# SNES2USB.net
KiCad netlist of a schematic drawn in EAGLE
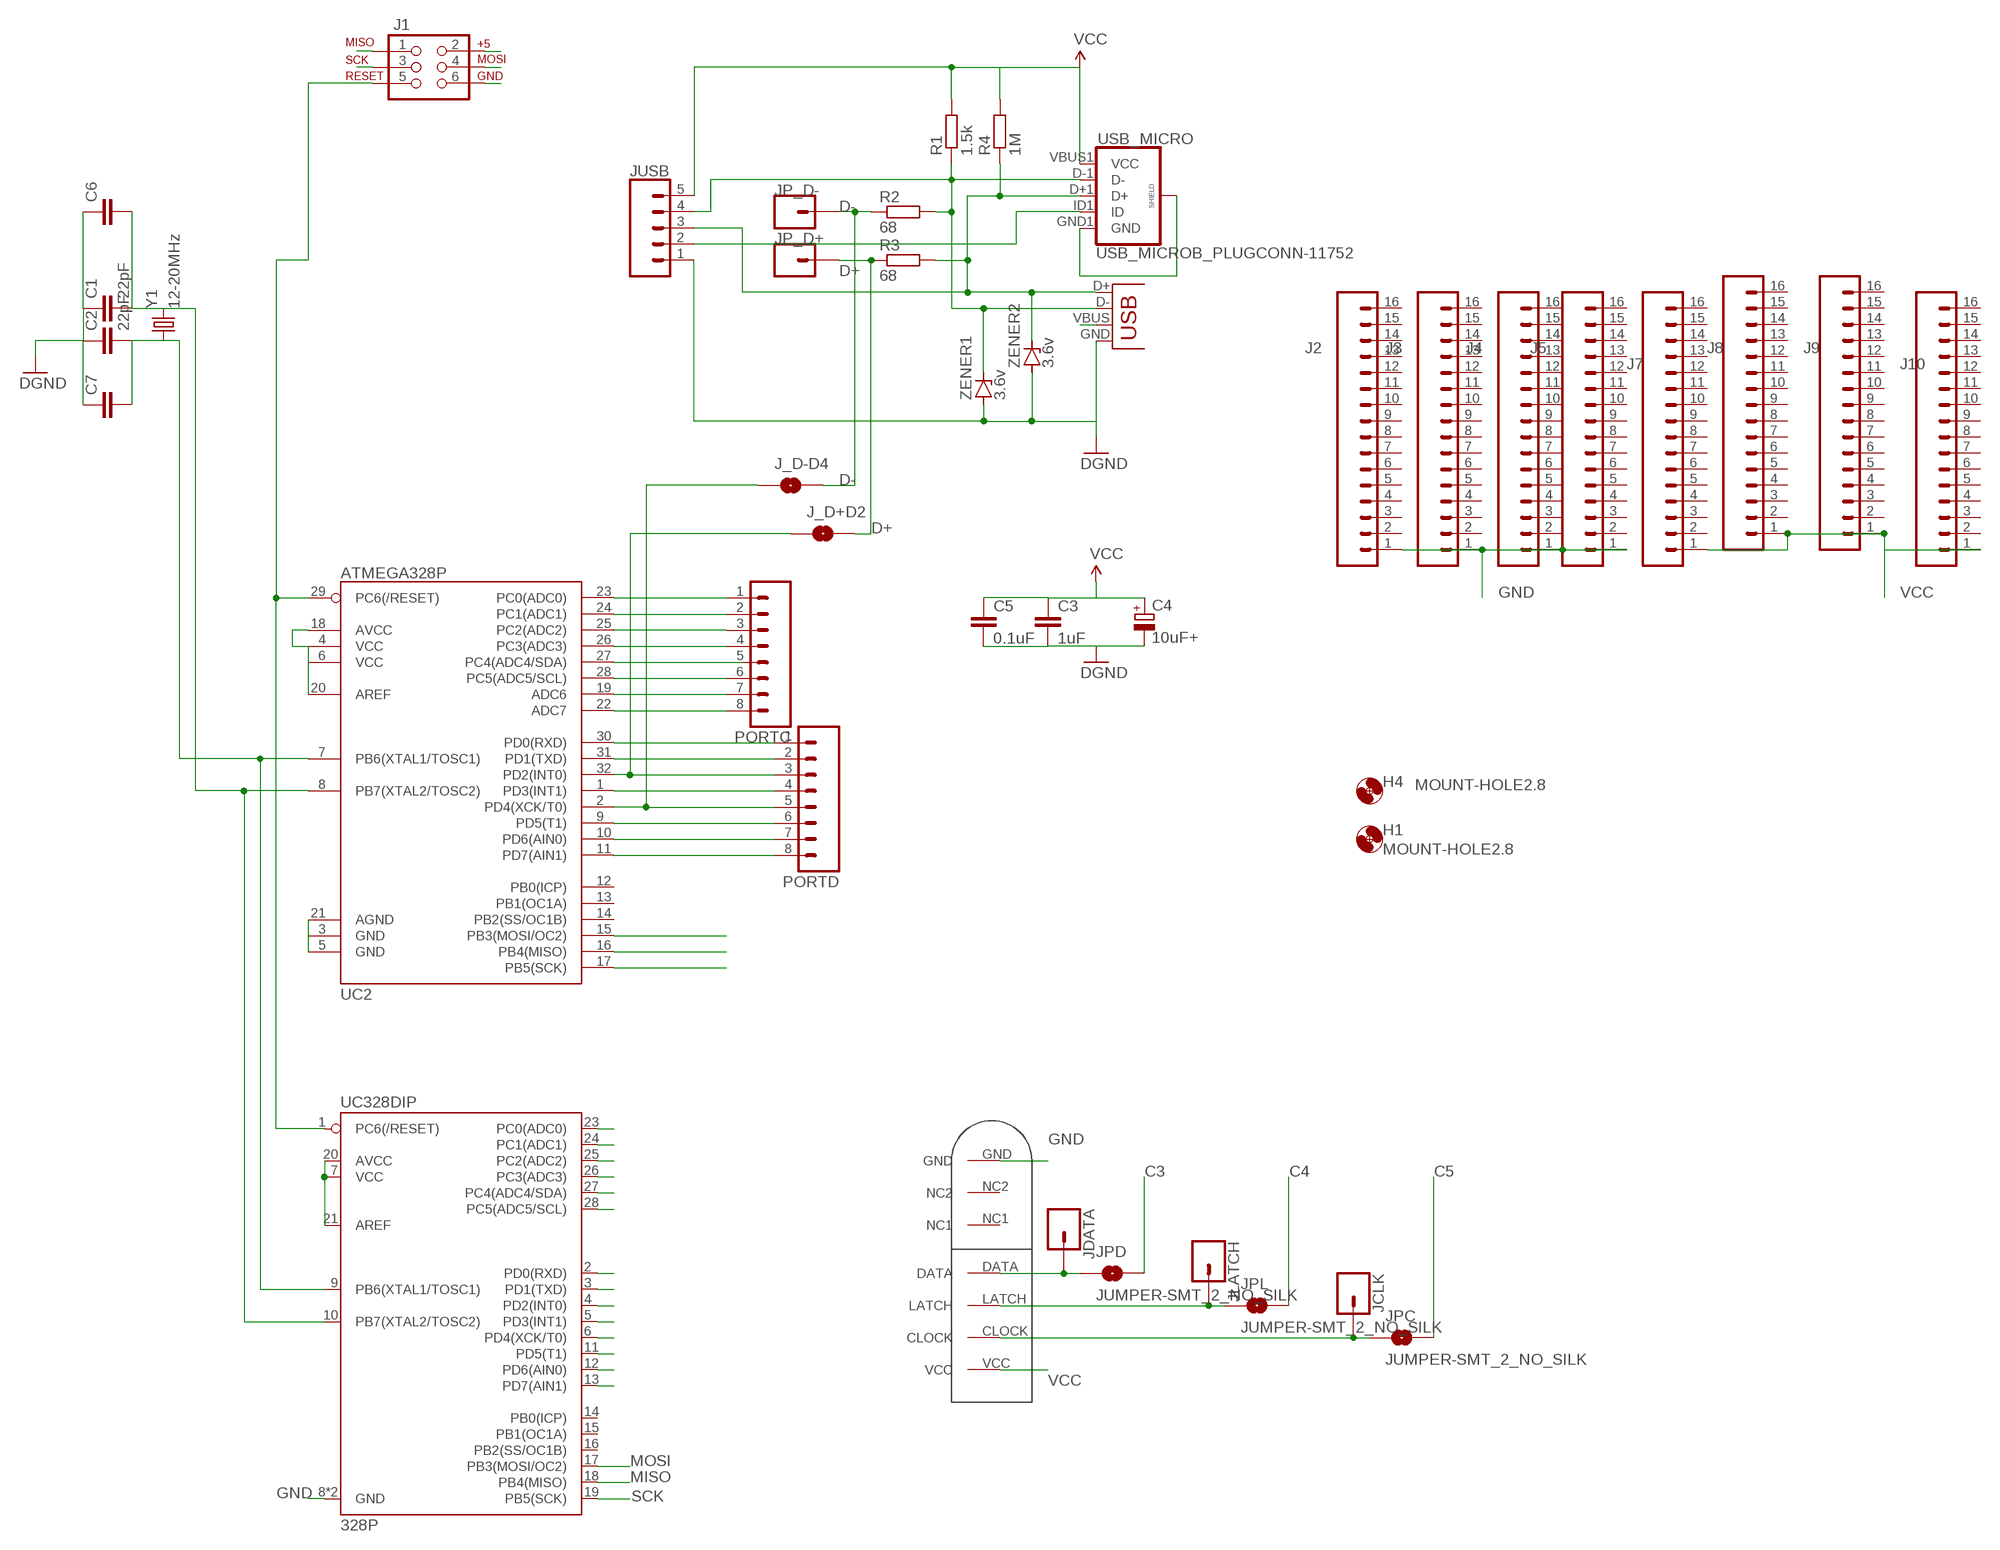
[diagram p0: schematic, sheet 1]

(export (version "E")
  (design (tool "Eeschema 10.0.6"))
  (components
    (comp (ref "C1")
      (value "22pF")
      (footprint "eagle-import:C025-024X044")
      (libsource (lib "eagle-import") (part "C-EU025-024X044"))
    )
    (comp (ref "C2")
      (value "22pF")
      (footprint "eagle-import:C025-024X044")
      (libsource (lib "eagle-import") (part "C-EU025-024X044"))
    )
    (comp (ref "C3")
      (value "1uF")
      (footprint "eagle-import:C025-024X044")
      (libsource (lib "eagle-import") (part "C-EU025-024X044"))
    )
    (comp (ref "C4")
      (value "10uF+")
      (footprint "eagle-import:E2-5")
      (libsource (lib "eagle-import") (part "CPOL-EUE2-5"))
    )
    (comp (ref "C5")
      (value "0.1uF")
      (footprint "eagle-import:C025-024X044")
      (libsource (lib "eagle-import") (part "C-EU025-024X044"))
    )
    (comp (ref "C6")
      (value "C-EUC1206K")
      (footprint "eagle-import:C1206K")
      (libsource (lib "eagle-import") (part "C-EUC1206K"))
    )
    (comp (ref "C7")
      (value "C-EUC1206K")
      (footprint "eagle-import:C1206K")
      (libsource (lib "eagle-import") (part "C-EUC1206K"))
    )
    (comp (ref "H1")
      (value "MOUNT-HOLE2.8")
      (footprint "eagle-import:2,8")
      (libsource (lib "eagle-import") (part "MOUNT-HOLE2.8"))
    )
    (comp (ref "H4")
      (value "MOUNT-HOLE2.8")
      (footprint "eagle-import:2,8")
      (libsource (lib "eagle-import") (part "MOUNT-HOLE2.8"))
    )
    (comp (ref "J1")
      (value "AVR_SPI_PRG_6PTH")
      (footprint "eagle-import:2X3")
      (libsource (lib "eagle-import") (part "AVR_SPI_PRG_6PTH"))
    )
    (comp (ref "J2")
      (value "CONN_161X16_NO_SILK")
      (footprint "eagle-import:1X16_NO_SILK")
      (libsource (lib "eagle-import") (part "CONN_161X16_NO_SILK"))
    )
    (comp (ref "J3")
      (value "CONN_161X16_NO_SILK")
      (footprint "eagle-import:1X16_NO_SILK")
      (libsource (lib "eagle-import") (part "CONN_161X16_NO_SILK"))
    )
    (comp (ref "J4")
      (value "CONN_161X16_NO_SILK")
      (footprint "eagle-import:1X16_NO_SILK")
      (libsource (lib "eagle-import") (part "CONN_161X16_NO_SILK"))
    )
    (comp (ref "J5")
      (value "CONN_161X16_NO_SILK")
      (footprint "eagle-import:1X16_NO_SILK")
      (libsource (lib "eagle-import") (part "CONN_161X16_NO_SILK"))
    )
    (comp (ref "J7")
      (value "CONN_161X16_NO_SILK")
      (footprint "eagle-import:1X16_NO_SILK")
      (libsource (lib "eagle-import") (part "CONN_161X16_NO_SILK"))
    )
    (comp (ref "J8")
      (value "CONN_161X16_NO_SILK")
      (footprint "eagle-import:1X16_NO_SILK")
      (libsource (lib "eagle-import") (part "CONN_161X16_NO_SILK"))
    )
    (comp (ref "J9")
      (value "CONN_161X16_NO_SILK")
      (footprint "eagle-import:1X16_NO_SILK")
      (libsource (lib "eagle-import") (part "CONN_161X16_NO_SILK"))
    )
    (comp (ref "J10")
      (value "CONN_161X16_NO_SILK")
      (footprint "eagle-import:1X16_NO_SILK")
      (libsource (lib "eagle-import") (part "CONN_161X16_NO_SILK"))
    )
    (comp (ref "JCLK")
      (value "CONN_01PTH_NO_SILK_YES_STOP")
      (footprint "eagle-import:1X01_NO_SILK")
      (libsource (lib "eagle-import") (part "CONN_01PTH_NO_SILK_YES_STOP"))
    )
    (comp (ref "JDATA")
      (value "CONN_01PTH_NO_SILK_YES_STOP")
      (footprint "eagle-import:1X01_NO_SILK")
      (libsource (lib "eagle-import") (part "CONN_01PTH_NO_SILK_YES_STOP"))
    )
    (comp (ref "JLATCH")
      (value "CONN_01PTH_NO_SILK_YES_STOP")
      (footprint "eagle-import:1X01_NO_SILK")
      (libsource (lib "eagle-import") (part "CONN_01PTH_NO_SILK_YES_STOP"))
    )
    (comp (ref "JPC")
      (value "JUMPER-SMT_2_NO_SILK")
      (footprint "eagle-import:SMT-JUMPER_2_NO_SILK")
      (libsource (lib "eagle-import") (part "JUMPER-SMT_2_NO_SILK"))
    )
    (comp (ref "JPD")
      (value "JUMPER-SMT_2_NO_SILK")
      (footprint "eagle-import:SMT-JUMPER_2_NO_SILK")
      (libsource (lib "eagle-import") (part "JUMPER-SMT_2_NO_SILK"))
    )
    (comp (ref "JPL")
      (value "JUMPER-SMT_2_NO_SILK")
      (footprint "eagle-import:SMT-JUMPER_2_NO_SILK")
      (libsource (lib "eagle-import") (part "JUMPER-SMT_2_NO_SILK"))
    )
    (comp (ref "JP_D+")
      (value "CONN_01PTH_NO_SILK_YES_STOP")
      (footprint "eagle-import:1X01_NO_SILK")
      (libsource (lib "eagle-import") (part "CONN_01PTH_NO_SILK_YES_STOP"))
    )
    (comp (ref "JP_D-")
      (value "CONN_01PTH_NO_SILK_YES_STOP")
      (footprint "eagle-import:1X01_NO_SILK")
      (libsource (lib "eagle-import") (part "CONN_01PTH_NO_SILK_YES_STOP"))
    )
    (comp (ref "JUSB")
      (value "CONN_05")
      (footprint "eagle-import:1X05")
      (libsource (lib "eagle-import") (part "CONN_05"))
    )
    (comp (ref "J_D+D2")
      (value "JUMPER-PAD-2-NOYES_SILK")
      (footprint "eagle-import:PAD-JUMPER-2-NO_YES_SILK")
      (libsource (lib "eagle-import") (part "JUMPER-PAD-2-NOYES_SILK"))
    )
    (comp (ref "J_D-D4")
      (value "JUMPER-PAD-2-NOYES_SILK")
      (footprint "eagle-import:PAD-JUMPER-2-NO_YES_SILK")
      (libsource (lib "eagle-import") (part "JUMPER-PAD-2-NOYES_SILK"))
    )
    (comp (ref "PORTC")
      (value "M081X08")
      (footprint "eagle-import:1X08")
      (libsource (lib "eagle-import") (part "M081X08"))
    )
    (comp (ref "PORTD")
      (value "M081X08")
      (footprint "eagle-import:1X08")
      (libsource (lib "eagle-import") (part "M081X08"))
    )
    (comp (ref "R1")
      (value "1.5k")
      (footprint "eagle-import:0204V")
      (libsource (lib "eagle-import") (part "R-EU_0204/2V"))
    )
    (comp (ref "R2")
      (value "68")
      (footprint "eagle-import:0204V")
      (libsource (lib "eagle-import") (part "R-EU_0204/2V"))
    )
    (comp (ref "R3")
      (value "68")
      (footprint "eagle-import:0204V")
      (libsource (lib "eagle-import") (part "R-EU_0204/2V"))
    )
    (comp (ref "R4")
      (value "1M")
      (footprint "eagle-import:0204V")
      (libsource (lib "eagle-import") (part "R-EU_0204/2V"))
    )
    (comp (ref "U$1")
      (value "SNES_JOYPAD_CONNECTOR")
      (footprint "eagle-import:SNES_PAD")
      (libsource (lib "eagle-import") (part "SNES_JOYPAD_CONNECTOR"))
    )
    (comp (ref "UC2")
      (value "ATMEGA328P")
      (footprint "eagle-import:TQFP32-08")
      (libsource (lib "eagle-import") (part "ATMEGA328_SMT"))
    )
    (comp (ref "UC328DIP")
      (value "328P")
      (footprint "eagle-import:DIP28")
      (libsource (lib "eagle-import") (part "ATMEGA328P_PDIP"))
    )
    (comp (ref "USB_MICRO")
      (value "USB_MICROB_PLUGCONN-11752")
      (footprint "eagle-import:USB-B-MICRO-SMD_V03")
      (libsource (lib "eagle-import") (part "USB_MICROB_PLUGCONN-11752"))
    )
    (comp (ref "USB_MINI")
      (value "USBSMD")
      (footprint "eagle-import:USB-MINIB")
      (libsource (lib "eagle-import") (part "USBSMD"))
    )
    (comp (ref "Y1")
      (value "12-20MHz")
      (footprint "eagle-import:HC49U-V")
      (libsource (lib "eagle-import") (part "CRYSTALHC49UV"))
    )
    (comp (ref "ZENER1")
      (value "3.6v")
      (footprint "eagle-import:ZDIO-2.5")
      (libsource (lib "eagle-import") (part "ZENER-DIODEZD-2.5"))
    )
    (comp (ref "ZENER2")
      (value "3.6v")
      (footprint "eagle-import:ZDIO-2.5")
      (libsource (lib "eagle-import") (part "ZENER-DIODEZD-2.5"))
    )
  )
  (nets
    (net (code "1") (name "/C0") (class "Default")
      (node (ref "PORTC") (pin "1") (pinfunction "1_1") (pintype "passive"))
      (node (ref "UC2") (pin "23") (pinfunction "PC0(ADC0)_23") (pintype "bidirectional"))
      (node (ref "UC328DIP") (pin "23") (pinfunction "PC0(ADC0)_23") (pintype "bidirectional"))
    )
    (net (code "2") (name "/C1") (class "Default")
      (node (ref "PORTC") (pin "2") (pinfunction "2_2") (pintype "passive"))
      (node (ref "UC2") (pin "24") (pinfunction "PC1(ADC1)_24") (pintype "bidirectional"))
      (node (ref "UC328DIP") (pin "24") (pinfunction "PC1(ADC1)_24") (pintype "bidirectional"))
    )
    (net (code "3") (name "/C3") (class "Default")
      (node (ref "JPD") (pin "2") (pinfunction "2_2") (pintype "passive"))
      (node (ref "PORTC") (pin "4") (pinfunction "4_4") (pintype "passive"))
      (node (ref "UC2") (pin "26") (pinfunction "PC3(ADC3)_26") (pintype "bidirectional"))
      (node (ref "UC328DIP") (pin "26") (pinfunction "PC3(ADC3)_26") (pintype "bidirectional"))
    )
    (net (code "4") (name "/C4") (class "Default")
      (node (ref "JPL") (pin "2") (pinfunction "2_2") (pintype "passive"))
      (node (ref "PORTC") (pin "5") (pinfunction "5_5") (pintype "passive"))
      (node (ref "UC2") (pin "27") (pinfunction "PC4(ADC4/SDA)_27") (pintype "bidirectional"))
      (node (ref "UC328DIP") (pin "27") (pinfunction "PC4(ADC4/SDA)_27") (pintype "bidirectional"))
    )
    (net (code "5") (name "/C5") (class "Default")
      (node (ref "JPC") (pin "2") (pinfunction "2_2") (pintype "passive"))
      (node (ref "PORTC") (pin "6") (pinfunction "6_6") (pintype "passive"))
      (node (ref "UC2") (pin "28") (pinfunction "PC5(ADC5/SCL)_28") (pintype "bidirectional"))
      (node (ref "UC328DIP") (pin "28") (pinfunction "PC5(ADC5/SCL)_28") (pintype "bidirectional"))
    )
    (net (code "6") (name "/D+") (class "Default")
      (node (ref "JP_D+") (pin "1") (pinfunction "1_1") (pintype "passive"))
      (node (ref "J_D+D2") (pin "2") (pinfunction "2_2") (pintype "passive"))
      (node (ref "R3") (pin "1") (pinfunction "1_1") (pintype "passive"))
    )
    (net (code "7") (name "/D-") (class "Default")
      (node (ref "JP_D-") (pin "1") (pinfunction "1_1") (pintype "passive"))
      (node (ref "J_D-D4") (pin "2") (pinfunction "2_2") (pintype "passive"))
      (node (ref "R2") (pin "1") (pinfunction "1_1") (pintype "passive"))
    )
    (net (code "8") (name "/D0") (class "Default")
      (node (ref "PORTD") (pin "1") (pinfunction "1_1") (pintype "passive"))
      (node (ref "UC2") (pin "30") (pinfunction "PD0(RXD)_30") (pintype "bidirectional"))
      (node (ref "UC328DIP") (pin "2") (pinfunction "PD0(RXD)_2") (pintype "bidirectional"))
    )
    (net (code "9") (name "/D1") (class "Default")
      (node (ref "PORTD") (pin "2") (pinfunction "2_2") (pintype "passive"))
      (node (ref "UC2") (pin "31") (pinfunction "PD1(TXD)_31") (pintype "bidirectional"))
      (node (ref "UC328DIP") (pin "3") (pinfunction "PD1(TXD)_3") (pintype "bidirectional"))
    )
    (net (code "10") (name "/D2") (class "Default")
      (node (ref "J_D+D2") (pin "1") (pinfunction "1_1") (pintype "passive"))
      (node (ref "PORTD") (pin "3") (pinfunction "3_3") (pintype "passive"))
      (node (ref "UC2") (pin "32") (pinfunction "PD2(INT0)_32") (pintype "bidirectional"))
      (node (ref "UC328DIP") (pin "4") (pinfunction "PD2(INT0)_4") (pintype "bidirectional"))
    )
    (net (code "11") (name "/D3") (class "Default")
      (node (ref "PORTD") (pin "4") (pinfunction "4_4") (pintype "passive"))
      (node (ref "UC2") (pin "1") (pinfunction "PD3(INT1)_1") (pintype "bidirectional"))
      (node (ref "UC328DIP") (pin "5") (pinfunction "PD3(INT1)_5") (pintype "bidirectional"))
    )
    (net (code "12") (name "/D4") (class "Default")
      (node (ref "J_D-D4") (pin "1") (pinfunction "1_1") (pintype "passive"))
      (node (ref "PORTD") (pin "5") (pinfunction "5_5") (pintype "passive"))
      (node (ref "UC2") (pin "2") (pinfunction "PD4(XCK/T0)_2") (pintype "bidirectional"))
      (node (ref "UC328DIP") (pin "6") (pinfunction "PD4(XCK/T0)_6") (pintype "bidirectional"))
    )
    (net (code "13") (name "/D5") (class "Default")
      (node (ref "PORTD") (pin "6") (pinfunction "6_6") (pintype "passive"))
      (node (ref "UC2") (pin "9") (pinfunction "PD5(T1)_9") (pintype "bidirectional"))
      (node (ref "UC328DIP") (pin "11") (pinfunction "PD5(T1)_11") (pintype "bidirectional"))
    )
    (net (code "14") (name "/D6") (class "Default")
      (node (ref "PORTD") (pin "7") (pinfunction "7_7") (pintype "passive"))
      (node (ref "UC2") (pin "10") (pinfunction "PD6(AIN0)_10") (pintype "bidirectional"))
      (node (ref "UC328DIP") (pin "12") (pinfunction "PD6(AIN0)_12") (pintype "bidirectional"))
    )
    (net (code "15") (name "/D7") (class "Default")
      (node (ref "PORTD") (pin "8") (pinfunction "8_8") (pintype "passive"))
      (node (ref "UC2") (pin "11") (pinfunction "PD7(AIN1)_11") (pintype "bidirectional"))
      (node (ref "UC328DIP") (pin "13") (pinfunction "PD7(AIN1)_13") (pintype "bidirectional"))
    )
    (net (code "16") (name "/MISO") (class "Default")
      (node (ref "J1") (pin "1") (pinfunction "1_1") (pintype "passive"))
      (node (ref "UC2") (pin "16") (pinfunction "PB4(MISO)_16") (pintype "bidirectional"))
      (node (ref "UC328DIP") (pin "18") (pinfunction "PB4(MISO)_18") (pintype "bidirectional"))
    )
    (net (code "17") (name "/MOSI") (class "Default")
      (node (ref "J1") (pin "4") (pinfunction "4_4") (pintype "passive"))
      (node (ref "UC2") (pin "15") (pinfunction "PB3(MOSI/OC2)_15") (pintype "bidirectional"))
      (node (ref "UC328DIP") (pin "17") (pinfunction "PB3(MOSI/OC2)_17") (pintype "bidirectional"))
    )
    (net (code "18") (name "/SCK") (class "Default")
      (node (ref "J1") (pin "3") (pinfunction "3_3") (pintype "passive"))
      (node (ref "UC2") (pin "17") (pinfunction "PB5(SCK)_17") (pintype "bidirectional"))
      (node (ref "UC328DIP") (pin "19") (pinfunction "PB5(SCK)_19") (pintype "bidirectional"))
    )
    (net (code "19") (name "DGND") (class "Default")
      (node (ref "C1") (pin "1") (pinfunction "1_1") (pintype "passive"))
      (node (ref "C2") (pin "1") (pinfunction "1_1") (pintype "passive"))
      (node (ref "C3") (pin "2") (pinfunction "2_2") (pintype "passive"))
      (node (ref "C4") (pin "-") (pinfunction "-_-") (pintype "passive"))
      (node (ref "C5") (pin "2") (pinfunction "2_2") (pintype "passive"))
      (node (ref "C6") (pin "1") (pinfunction "1_1") (pintype "passive"))
      (node (ref "C7") (pin "1") (pinfunction "1_1") (pintype "passive"))
      (node (ref "J1") (pin "6") (pinfunction "6_6") (pintype "passive"))
      (node (ref "J2") (pin "1") (pinfunction "1_1") (pintype "passive"))
      (node (ref "J3") (pin "1") (pinfunction "1_1") (pintype "passive"))
      (node (ref "J4") (pin "1") (pinfunction "1_1") (pintype "passive"))
      (node (ref "J5") (pin "1") (pinfunction "1_1") (pintype "passive"))
      (node (ref "JUSB") (pin "1") (pinfunction "1_1") (pintype "passive"))
      (node (ref "U$1") (pin "GND") (pinfunction "GND_GND") (pintype "bidirectional"))
      (node (ref "UC2") (pin "21") (pinfunction "AGND_21") (pintype "bidirectional"))
      (node (ref "UC2") (pin "3") (pinfunction "GND_3") (pintype "bidirectional"))
      (node (ref "UC2") (pin "5") (pinfunction "GND_5") (pintype "bidirectional"))
      (node (ref "UC328DIP") (pin "22") (pinfunction "GND_22") (pintype "bidirectional"))
      (node (ref "UC328DIP") (pin "8") (pinfunction "GND_8") (pintype "bidirectional"))
      (node (ref "USB_MICRO") (pin "GND1") (pinfunction "GND_GND1") (pintype "bidirectional"))
      (node (ref "USB_MICRO") (pin "SHIELD1") (pinfunction "SHIELD_SHIELD1") (pintype "bidirectional"))
      (node (ref "USB_MICRO") (pin "SHIELD2") (pinfunction "SHIELD_SHIELD2") (pintype "bidirectional"))
      (node (ref "USB_MICRO") (pin "SHIELD3") (pinfunction "SHIELD_SHIELD3") (pintype "bidirectional"))
      (node (ref "USB_MINI") (pin "GND") (pinfunction "GND_GND") (pintype "bidirectional"))
      (node (ref "ZENER1") (pin "A") (pinfunction "A_A") (pintype "passive"))
      (node (ref "ZENER2") (pin "A") (pinfunction "A_A") (pintype "passive"))
    )
    (net (code "20") (name "Net-(JCLK-Pad1)") (class "Default")
      (node (ref "JCLK") (pin "1") (pinfunction "1_1") (pintype "passive"))
      (node (ref "JPC") (pin "1") (pinfunction "1_1") (pintype "passive"))
      (node (ref "U$1") (pin "CLOCK") (pinfunction "CLOCK_CLOCK") (pintype "bidirectional"))
    )
    (net (code "21") (name "Net-(JDATA-Pad1)") (class "Default")
      (node (ref "JDATA") (pin "1") (pinfunction "1_1") (pintype "passive"))
      (node (ref "JPD") (pin "1") (pinfunction "1_1") (pintype "passive"))
      (node (ref "U$1") (pin "DATA") (pinfunction "DATA_DATA") (pintype "bidirectional"))
    )
    (net (code "22") (name "Net-(JLATCH-Pad1)") (class "Default")
      (node (ref "JLATCH") (pin "1") (pinfunction "1_1") (pintype "passive"))
      (node (ref "JPL") (pin "1") (pinfunction "1_1") (pintype "passive"))
      (node (ref "U$1") (pin "LATCH") (pinfunction "LATCH_LATCH") (pintype "bidirectional"))
    )
    (net (code "23") (name "Net-(UC2-ADC6)") (class "Default")
      (node (ref "PORTC") (pin "7") (pinfunction "7_7") (pintype "passive"))
      (node (ref "UC2") (pin "19") (pinfunction "ADC6_19") (pintype "bidirectional"))
    )
    (net (code "24") (name "Net-(UC2-ADC7)") (class "Default")
      (node (ref "PORTC") (pin "8") (pinfunction "8_8") (pintype "passive"))
      (node (ref "UC2") (pin "22") (pinfunction "ADC7_22") (pintype "bidirectional"))
    )
    (net (code "25") (name "Net-(UC2-PB6(XTAL1{slash}TOSC1))") (class "Default")
      (node (ref "C2") (pin "2") (pinfunction "2_2") (pintype "passive"))
      (node (ref "C7") (pin "2") (pinfunction "2_2") (pintype "passive"))
      (node (ref "UC2") (pin "7") (pinfunction "PB6(XTAL1/TOSC1)_7") (pintype "bidirectional"))
      (node (ref "UC328DIP") (pin "9") (pinfunction "PB6(XTAL1/TOSC1)_9") (pintype "bidirectional"))
      (node (ref "Y1") (pin "1") (pinfunction "1_1") (pintype "passive"))
    )
    (net (code "26") (name "Net-(UC2-PB7(XTAL2{slash}TOSC2))") (class "Default")
      (node (ref "C1") (pin "2") (pinfunction "2_2") (pintype "passive"))
      (node (ref "C6") (pin "2") (pinfunction "2_2") (pintype "passive"))
      (node (ref "UC2") (pin "8") (pinfunction "PB7(XTAL2/TOSC2)_8") (pintype "bidirectional"))
      (node (ref "UC328DIP") (pin "10") (pinfunction "PB7(XTAL2/TOSC2)_10") (pintype "bidirectional"))
      (node (ref "Y1") (pin "2") (pinfunction "2_2") (pintype "passive"))
    )
    (net (code "27") (name "Net-(UC2-PC2(ADC2))") (class "Default")
      (node (ref "PORTC") (pin "3") (pinfunction "3_3") (pintype "passive"))
      (node (ref "UC2") (pin "25") (pinfunction "PC2(ADC2)_25") (pintype "bidirectional"))
    )
    (net (code "28") (name "Net-(UC2-PC6({slash}RESET))") (class "Default")
      (node (ref "J1") (pin "5") (pinfunction "5_5") (pintype "passive"))
      (node (ref "UC2") (pin "29") (pinfunction "PC6(/RESET)_29") (pintype "bidirectional"))
      (node (ref "UC328DIP") (pin "1") (pinfunction "PC6(/RESET)_1") (pintype "bidirectional"))
    )
    (net (code "29") (name "Net-(USB_MICRO-D+)") (class "Default")
      (node (ref "JUSB") (pin "3") (pinfunction "3_3") (pintype "passive"))
      (node (ref "R3") (pin "2") (pinfunction "2_2") (pintype "passive"))
      (node (ref "R4") (pin "1") (pinfunction "1_1") (pintype "passive"))
      (node (ref "USB_MICRO") (pin "D+1") (pinfunction "D+_D+1") (pintype "bidirectional"))
      (node (ref "USB_MINI") (pin "D+") (pinfunction "D+_D+") (pintype "bidirectional"))
      (node (ref "ZENER2") (pin "C") (pinfunction "C_C") (pintype "passive"))
    )
    (net (code "30") (name "Net-(USB_MICRO-D-)") (class "Default")
      (node (ref "JUSB") (pin "4") (pinfunction "4_4") (pintype "passive"))
      (node (ref "R1") (pin "1") (pinfunction "1_1") (pintype "passive"))
      (node (ref "R2") (pin "2") (pinfunction "2_2") (pintype "passive"))
      (node (ref "USB_MICRO") (pin "D-1") (pinfunction "D-_D-1") (pintype "bidirectional"))
      (node (ref "USB_MINI") (pin "D-") (pinfunction "D-_D-") (pintype "bidirectional"))
      (node (ref "ZENER1") (pin "C") (pinfunction "C_C") (pintype "passive"))
    )
    (net (code "31") (name "Net-(USB_MICRO-ID)") (class "Default")
      (node (ref "JUSB") (pin "2") (pinfunction "2_2") (pintype "passive"))
      (node (ref "USB_MICRO") (pin "ID1") (pinfunction "ID_ID1") (pintype "bidirectional"))
    )
    (net (code "32") (name "VCC") (class "Default")
      (node (ref "C3") (pin "1") (pinfunction "1_1") (pintype "passive"))
      (node (ref "C4") (pin "+") (pinfunction "+_+") (pintype "passive"))
      (node (ref "C5") (pin "1") (pinfunction "1_1") (pintype "passive"))
      (node (ref "J1") (pin "2") (pinfunction "2_2") (pintype "passive"))
      (node (ref "J10") (pin "1") (pinfunction "1_1") (pintype "passive"))
      (node (ref "J7") (pin "1") (pinfunction "1_1") (pintype "passive"))
      (node (ref "J8") (pin "1") (pinfunction "1_1") (pintype "passive"))
      (node (ref "J9") (pin "1") (pinfunction "1_1") (pintype "passive"))
      (node (ref "JUSB") (pin "5") (pinfunction "5_5") (pintype "passive"))
      (node (ref "R1") (pin "2") (pinfunction "2_2") (pintype "passive"))
      (node (ref "R4") (pin "2") (pinfunction "2_2") (pintype "passive"))
      (node (ref "U$1") (pin "VCC") (pinfunction "VCC_VCC") (pintype "bidirectional"))
      (node (ref "UC2") (pin "18") (pinfunction "AVCC_18") (pintype "bidirectional"))
      (node (ref "UC2") (pin "20") (pinfunction "AREF_20") (pintype "bidirectional"))
      (node (ref "UC2") (pin "4") (pinfunction "VCC_4") (pintype "bidirectional"))
      (node (ref "UC2") (pin "6") (pinfunction "VCC_6") (pintype "bidirectional"))
      (node (ref "UC328DIP") (pin "20") (pinfunction "AVCC_20") (pintype "bidirectional"))
      (node (ref "UC328DIP") (pin "21") (pinfunction "AREF_21") (pintype "bidirectional"))
      (node (ref "UC328DIP") (pin "7") (pinfunction "VCC_7") (pintype "bidirectional"))
      (node (ref "USB_MICRO") (pin "VBUS1") (pinfunction "VCC_VBUS1") (pintype "bidirectional"))
      (node (ref "USB_MINI") (pin "VBUS") (pinfunction "VBUS_VBUS") (pintype "bidirectional"))
    )
    (net (code "33") (name "unconnected-(J2-Pad2)") (class "Default")
      (node (ref "J2") (pin "2") (pinfunction "2_2") (pintype "passive"))
    )
    (net (code "34") (name "unconnected-(J2-Pad3)") (class "Default")
      (node (ref "J2") (pin "3") (pinfunction "3_3") (pintype "passive"))
    )
    (net (code "35") (name "unconnected-(J2-Pad4)") (class "Default")
      (node (ref "J2") (pin "4") (pinfunction "4_4") (pintype "passive"))
    )
    (net (code "36") (name "unconnected-(J2-Pad5)") (class "Default")
      (node (ref "J2") (pin "5") (pinfunction "5_5") (pintype "passive"))
    )
    (net (code "37") (name "unconnected-(J2-Pad6)") (class "Default")
      (node (ref "J2") (pin "6") (pinfunction "6_6") (pintype "passive"))
    )
    (net (code "38") (name "unconnected-(J2-Pad7)") (class "Default")
      (node (ref "J2") (pin "7") (pinfunction "7_7") (pintype "passive"))
    )
    (net (code "39") (name "unconnected-(J2-Pad8)") (class "Default")
      (node (ref "J2") (pin "8") (pinfunction "8_8") (pintype "passive"))
    )
    (net (code "40") (name "unconnected-(J2-Pad9)") (class "Default")
      (node (ref "J2") (pin "9") (pinfunction "9_9") (pintype "passive"))
    )
    (net (code "41") (name "unconnected-(J2-Pad10)") (class "Default")
      (node (ref "J2") (pin "10") (pinfunction "10_10") (pintype "passive"))
    )
    (net (code "42") (name "unconnected-(J2-Pad11)") (class "Default")
      (node (ref "J2") (pin "11") (pinfunction "11_11") (pintype "passive"))
    )
    (net (code "43") (name "unconnected-(J2-Pad12)") (class "Default")
      (node (ref "J2") (pin "12") (pinfunction "12_12") (pintype "passive"))
    )
    (net (code "44") (name "unconnected-(J2-Pad13)") (class "Default")
      (node (ref "J2") (pin "13") (pinfunction "13_13") (pintype "passive"))
    )
    (net (code "45") (name "unconnected-(J2-Pad14)") (class "Default")
      (node (ref "J2") (pin "14") (pinfunction "14_14") (pintype "passive"))
    )
    (net (code "46") (name "unconnected-(J2-Pad15)") (class "Default")
      (node (ref "J2") (pin "15") (pinfunction "15_15") (pintype "passive"))
    )
    (net (code "47") (name "unconnected-(J2-Pad16)") (class "Default")
      (node (ref "J2") (pin "16") (pinfunction "16_16") (pintype "passive"))
    )
    (net (code "48") (name "unconnected-(J3-Pad2)") (class "Default")
      (node (ref "J3") (pin "2") (pinfunction "2_2") (pintype "passive"))
    )
    (net (code "49") (name "unconnected-(J3-Pad3)") (class "Default")
      (node (ref "J3") (pin "3") (pinfunction "3_3") (pintype "passive"))
    )
    (net (code "50") (name "unconnected-(J3-Pad4)") (class "Default")
      (node (ref "J3") (pin "4") (pinfunction "4_4") (pintype "passive"))
    )
    (net (code "51") (name "unconnected-(J3-Pad5)") (class "Default")
      (node (ref "J3") (pin "5") (pinfunction "5_5") (pintype "passive"))
    )
    (net (code "52") (name "unconnected-(J3-Pad6)") (class "Default")
      (node (ref "J3") (pin "6") (pinfunction "6_6") (pintype "passive"))
    )
    (net (code "53") (name "unconnected-(J3-Pad7)") (class "Default")
      (node (ref "J3") (pin "7") (pinfunction "7_7") (pintype "passive"))
    )
    (net (code "54") (name "unconnected-(J3-Pad8)") (class "Default")
      (node (ref "J3") (pin "8") (pinfunction "8_8") (pintype "passive"))
    )
    (net (code "55") (name "unconnected-(J3-Pad9)") (class "Default")
      (node (ref "J3") (pin "9") (pinfunction "9_9") (pintype "passive"))
    )
    (net (code "56") (name "unconnected-(J3-Pad10)") (class "Default")
      (node (ref "J3") (pin "10") (pinfunction "10_10") (pintype "passive"))
    )
    (net (code "57") (name "unconnected-(J3-Pad11)") (class "Default")
      (node (ref "J3") (pin "11") (pinfunction "11_11") (pintype "passive"))
    )
    (net (code "58") (name "unconnected-(J3-Pad12)") (class "Default")
      (node (ref "J3") (pin "12") (pinfunction "12_12") (pintype "passive"))
    )
    (net (code "59") (name "unconnected-(J3-Pad13)") (class "Default")
      (node (ref "J3") (pin "13") (pinfunction "13_13") (pintype "passive"))
    )
    (net (code "60") (name "unconnected-(J3-Pad14)") (class "Default")
      (node (ref "J3") (pin "14") (pinfunction "14_14") (pintype "passive"))
    )
    (net (code "61") (name "unconnected-(J3-Pad15)") (class "Default")
      (node (ref "J3") (pin "15") (pinfunction "15_15") (pintype "passive"))
    )
    (net (code "62") (name "unconnected-(J3-Pad16)") (class "Default")
      (node (ref "J3") (pin "16") (pinfunction "16_16") (pintype "passive"))
    )
    (net (code "63") (name "unconnected-(J4-Pad2)") (class "Default")
      (node (ref "J4") (pin "2") (pinfunction "2_2") (pintype "passive"))
    )
    (net (code "64") (name "unconnected-(J4-Pad3)") (class "Default")
      (node (ref "J4") (pin "3") (pinfunction "3_3") (pintype "passive"))
    )
    (net (code "65") (name "unconnected-(J4-Pad4)") (class "Default")
      (node (ref "J4") (pin "4") (pinfunction "4_4") (pintype "passive"))
    )
    (net (code "66") (name "unconnected-(J4-Pad5)") (class "Default")
      (node (ref "J4") (pin "5") (pinfunction "5_5") (pintype "passive"))
    )
    (net (code "67") (name "unconnected-(J4-Pad6)") (class "Default")
      (node (ref "J4") (pin "6") (pinfunction "6_6") (pintype "passive"))
    )
    (net (code "68") (name "unconnected-(J4-Pad7)") (class "Default")
      (node (ref "J4") (pin "7") (pinfunction "7_7") (pintype "passive"))
    )
    (net (code "69") (name "unconnected-(J4-Pad8)") (class "Default")
      (node (ref "J4") (pin "8") (pinfunction "8_8") (pintype "passive"))
    )
    (net (code "70") (name "unconnected-(J4-Pad9)") (class "Default")
      (node (ref "J4") (pin "9") (pinfunction "9_9") (pintype "passive"))
    )
    (net (code "71") (name "unconnected-(J4-Pad10)") (class "Default")
      (node (ref "J4") (pin "10") (pinfunction "10_10") (pintype "passive"))
    )
    (net (code "72") (name "unconnected-(J4-Pad11)") (class "Default")
      (node (ref "J4") (pin "11") (pinfunction "11_11") (pintype "passive"))
    )
    (net (code "73") (name "unconnected-(J4-Pad12)") (class "Default")
      (node (ref "J4") (pin "12") (pinfunction "12_12") (pintype "passive"))
    )
    (net (code "74") (name "unconnected-(J4-Pad13)") (class "Default")
      (node (ref "J4") (pin "13") (pinfunction "13_13") (pintype "passive"))
    )
    (net (code "75") (name "unconnected-(J4-Pad14)") (class "Default")
      (node (ref "J4") (pin "14") (pinfunction "14_14") (pintype "passive"))
    )
    (net (code "76") (name "unconnected-(J4-Pad15)") (class "Default")
      (node (ref "J4") (pin "15") (pinfunction "15_15") (pintype "passive"))
    )
    (net (code "77") (name "unconnected-(J4-Pad16)") (class "Default")
      (node (ref "J4") (pin "16") (pinfunction "16_16") (pintype "passive"))
    )
    (net (code "78") (name "unconnected-(J5-Pad2)") (class "Default")
      (node (ref "J5") (pin "2") (pinfunction "2_2") (pintype "passive"))
    )
    (net (code "79") (name "unconnected-(J5-Pad3)") (class "Default")
      (node (ref "J5") (pin "3") (pinfunction "3_3") (pintype "passive"))
    )
    (net (code "80") (name "unconnected-(J5-Pad4)") (class "Default")
      (node (ref "J5") (pin "4") (pinfunction "4_4") (pintype "passive"))
    )
    (net (code "81") (name "unconnected-(J5-Pad5)") (class "Default")
      (node (ref "J5") (pin "5") (pinfunction "5_5") (pintype "passive"))
    )
    (net (code "82") (name "unconnected-(J5-Pad6)") (class "Default")
      (node (ref "J5") (pin "6") (pinfunction "6_6") (pintype "passive"))
    )
    (net (code "83") (name "unconnected-(J5-Pad7)") (class "Default")
      (node (ref "J5") (pin "7") (pinfunction "7_7") (pintype "passive"))
    )
    (net (code "84") (name "unconnected-(J5-Pad8)") (class "Default")
      (node (ref "J5") (pin "8") (pinfunction "8_8") (pintype "passive"))
    )
    (net (code "85") (name "unconnected-(J5-Pad9)") (class "Default")
      (node (ref "J5") (pin "9") (pinfunction "9_9") (pintype "passive"))
    )
    (net (code "86") (name "unconnected-(J5-Pad10)") (class "Default")
      (node (ref "J5") (pin "10") (pinfunction "10_10") (pintype "passive"))
    )
    (net (code "87") (name "unconnected-(J5-Pad11)") (class "Default")
      (node (ref "J5") (pin "11") (pinfunction "11_11") (pintype "passive"))
    )
    (net (code "88") (name "unconnected-(J5-Pad12)") (class "Default")
      (node (ref "J5") (pin "12") (pinfunction "12_12") (pintype "passive"))
    )
    (net (code "89") (name "unconnected-(J5-Pad13)") (class "Default")
      (node (ref "J5") (pin "13") (pinfunction "13_13") (pintype "passive"))
    )
    (net (code "90") (name "unconnected-(J5-Pad14)") (class "Default")
      (node (ref "J5") (pin "14") (pinfunction "14_14") (pintype "passive"))
    )
    (net (code "91") (name "unconnected-(J5-Pad15)") (class "Default")
      (node (ref "J5") (pin "15") (pinfunction "15_15") (pintype "passive"))
    )
    (net (code "92") (name "unconnected-(J5-Pad16)") (class "Default")
      (node (ref "J5") (pin "16") (pinfunction "16_16") (pintype "passive"))
    )
    (net (code "93") (name "unconnected-(J7-Pad2)") (class "Default")
      (node (ref "J7") (pin "2") (pinfunction "2_2") (pintype "passive"))
    )
    (net (code "94") (name "unconnected-(J7-Pad3)") (class "Default")
      (node (ref "J7") (pin "3") (pinfunction "3_3") (pintype "passive"))
    )
    (net (code "95") (name "unconnected-(J7-Pad4)") (class "Default")
      (node (ref "J7") (pin "4") (pinfunction "4_4") (pintype "passive"))
    )
    (net (code "96") (name "unconnected-(J7-Pad5)") (class "Default")
      (node (ref "J7") (pin "5") (pinfunction "5_5") (pintype "passive"))
    )
    (net (code "97") (name "unconnected-(J7-Pad6)") (class "Default")
      (node (ref "J7") (pin "6") (pinfunction "6_6") (pintype "passive"))
    )
    (net (code "98") (name "unconnected-(J7-Pad7)") (class "Default")
      (node (ref "J7") (pin "7") (pinfunction "7_7") (pintype "passive"))
    )
    (net (code "99") (name "unconnected-(J7-Pad8)") (class "Default")
      (node (ref "J7") (pin "8") (pinfunction "8_8") (pintype "passive"))
    )
    (net (code "100") (name "unconnected-(J7-Pad9)") (class "Default")
      (node (ref "J7") (pin "9") (pinfunction "9_9") (pintype "passive"))
    )
    (net (code "101") (name "unconnected-(J7-Pad10)") (class "Default")
      (node (ref "J7") (pin "10") (pinfunction "10_10") (pintype "passive"))
    )
    (net (code "102") (name "unconnected-(J7-Pad11)") (class "Default")
      (node (ref "J7") (pin "11") (pinfunction "11_11") (pintype "passive"))
    )
    (net (code "103") (name "unconnected-(J7-Pad12)") (class "Default")
      (node (ref "J7") (pin "12") (pinfunction "12_12") (pintype "passive"))
    )
    (net (code "104") (name "unconnected-(J7-Pad13)") (class "Default")
      (node (ref "J7") (pin "13") (pinfunction "13_13") (pintype "passive"))
    )
    (net (code "105") (name "unconnected-(J7-Pad14)") (class "Default")
      (node (ref "J7") (pin "14") (pinfunction "14_14") (pintype "passive"))
    )
    (net (code "106") (name "unconnected-(J7-Pad15)") (class "Default")
      (node (ref "J7") (pin "15") (pinfunction "15_15") (pintype "passive"))
    )
    (net (code "107") (name "unconnected-(J7-Pad16)") (class "Default")
      (node (ref "J7") (pin "16") (pinfunction "16_16") (pintype "passive"))
    )
    (net (code "108") (name "unconnected-(J8-Pad2)") (class "Default")
      (node (ref "J8") (pin "2") (pinfunction "2_2") (pintype "passive"))
    )
    (net (code "109") (name "unconnected-(J8-Pad3)") (class "Default")
      (node (ref "J8") (pin "3") (pinfunction "3_3") (pintype "passive"))
    )
    (net (code "110") (name "unconnected-(J8-Pad4)") (class "Default")
      (node (ref "J8") (pin "4") (pinfunction "4_4") (pintype "passive"))
    )
    (net (code "111") (name "unconnected-(J8-Pad5)") (class "Default")
      (node (ref "J8") (pin "5") (pinfunction "5_5") (pintype "passive"))
    )
    (net (code "112") (name "unconnected-(J8-Pad6)") (class "Default")
      (node (ref "J8") (pin "6") (pinfunction "6_6") (pintype "passive"))
    )
    (net (code "113") (name "unconnected-(J8-Pad7)") (class "Default")
      (node (ref "J8") (pin "7") (pinfunction "7_7") (pintype "passive"))
    )
    (net (code "114") (name "unconnected-(J8-Pad8)") (class "Default")
      (node (ref "J8") (pin "8") (pinfunction "8_8") (pintype "passive"))
    )
    (net (code "115") (name "unconnected-(J8-Pad9)") (class "Default")
      (node (ref "J8") (pin "9") (pinfunction "9_9") (pintype "passive"))
    )
    (net (code "116") (name "unconnected-(J8-Pad10)") (class "Default")
      (node (ref "J8") (pin "10") (pinfunction "10_10") (pintype "passive"))
    )
    (net (code "117") (name "unconnected-(J8-Pad11)") (class "Default")
      (node (ref "J8") (pin "11") (pinfunction "11_11") (pintype "passive"))
    )
    (net (code "118") (name "unconnected-(J8-Pad12)") (class "Default")
      (node (ref "J8") (pin "12") (pinfunction "12_12") (pintype "passive"))
    )
    (net (code "119") (name "unconnected-(J8-Pad13)") (class "Default")
      (node (ref "J8") (pin "13") (pinfunction "13_13") (pintype "passive"))
    )
    (net (code "120") (name "unconnected-(J8-Pad14)") (class "Default")
      (node (ref "J8") (pin "14") (pinfunction "14_14") (pintype "passive"))
    )
    (net (code "121") (name "unconnected-(J8-Pad15)") (class "Default")
      (node (ref "J8") (pin "15") (pinfunction "15_15") (pintype "passive"))
    )
    (net (code "122") (name "unconnected-(J8-Pad16)") (class "Default")
      (node (ref "J8") (pin "16") (pinfunction "16_16") (pintype "passive"))
    )
    (net (code "123") (name "unconnected-(J9-Pad2)") (class "Default")
      (node (ref "J9") (pin "2") (pinfunction "2_2") (pintype "passive"))
    )
    (net (code "124") (name "unconnected-(J9-Pad3)") (class "Default")
      (node (ref "J9") (pin "3") (pinfunction "3_3") (pintype "passive"))
    )
    (net (code "125") (name "unconnected-(J9-Pad4)") (class "Default")
      (node (ref "J9") (pin "4") (pinfunction "4_4") (pintype "passive"))
    )
    (net (code "126") (name "unconnected-(J9-Pad5)") (class "Default")
      (node (ref "J9") (pin "5") (pinfunction "5_5") (pintype "passive"))
    )
    (net (code "127") (name "unconnected-(J9-Pad6)") (class "Default")
      (node (ref "J9") (pin "6") (pinfunction "6_6") (pintype "passive"))
    )
    (net (code "128") (name "unconnected-(J9-Pad7)") (class "Default")
      (node (ref "J9") (pin "7") (pinfunction "7_7") (pintype "passive"))
    )
    (net (code "129") (name "unconnected-(J9-Pad8)") (class "Default")
      (node (ref "J9") (pin "8") (pinfunction "8_8") (pintype "passive"))
    )
    (net (code "130") (name "unconnected-(J9-Pad9)") (class "Default")
      (node (ref "J9") (pin "9") (pinfunction "9_9") (pintype "passive"))
    )
    (net (code "131") (name "unconnected-(J9-Pad10)") (class "Default")
      (node (ref "J9") (pin "10") (pinfunction "10_10") (pintype "passive"))
    )
    (net (code "132") (name "unconnected-(J9-Pad11)") (class "Default")
      (node (ref "J9") (pin "11") (pinfunction "11_11") (pintype "passive"))
    )
    (net (code "133") (name "unconnected-(J9-Pad12)") (class "Default")
      (node (ref "J9") (pin "12") (pinfunction "12_12") (pintype "passive"))
    )
    (net (code "134") (name "unconnected-(J9-Pad13)") (class "Default")
      (node (ref "J9") (pin "13") (pinfunction "13_13") (pintype "passive"))
    )
    (net (code "135") (name "unconnected-(J9-Pad14)") (class "Default")
      (node (ref "J9") (pin "14") (pinfunction "14_14") (pintype "passive"))
    )
    (net (code "136") (name "unconnected-(J9-Pad15)") (class "Default")
      (node (ref "J9") (pin "15") (pinfunction "15_15") (pintype "passive"))
    )
    (net (code "137") (name "unconnected-(J9-Pad16)") (class "Default")
      (node (ref "J9") (pin "16") (pinfunction "16_16") (pintype "passive"))
    )
    (net (code "138") (name "unconnected-(J10-Pad2)") (class "Default")
      (node (ref "J10") (pin "2") (pinfunction "2_2") (pintype "passive"))
    )
    (net (code "139") (name "unconnected-(J10-Pad3)") (class "Default")
      (node (ref "J10") (pin "3") (pinfunction "3_3") (pintype "passive"))
    )
    (net (code "140") (name "unconnected-(J10-Pad4)") (class "Default")
      (node (ref "J10") (pin "4") (pinfunction "4_4") (pintype "passive"))
    )
    (net (code "141") (name "unconnected-(J10-Pad5)") (class "Default")
      (node (ref "J10") (pin "5") (pinfunction "5_5") (pintype "passive"))
    )
    (net (code "142") (name "unconnected-(J10-Pad6)") (class "Default")
      (node (ref "J10") (pin "6") (pinfunction "6_6") (pintype "passive"))
    )
    (net (code "143") (name "unconnected-(J10-Pad7)") (class "Default")
      (node (ref "J10") (pin "7") (pinfunction "7_7") (pintype "passive"))
    )
    (net (code "144") (name "unconnected-(J10-Pad8)") (class "Default")
      (node (ref "J10") (pin "8") (pinfunction "8_8") (pintype "passive"))
    )
    (net (code "145") (name "unconnected-(J10-Pad9)") (class "Default")
      (node (ref "J10") (pin "9") (pinfunction "9_9") (pintype "passive"))
    )
    (net (code "146") (name "unconnected-(J10-Pad10)") (class "Default")
      (node (ref "J10") (pin "10") (pinfunction "10_10") (pintype "passive"))
    )
    (net (code "147") (name "unconnected-(J10-Pad11)") (class "Default")
      (node (ref "J10") (pin "11") (pinfunction "11_11") (pintype "passive"))
    )
    (net (code "148") (name "unconnected-(J10-Pad12)") (class "Default")
      (node (ref "J10") (pin "12") (pinfunction "12_12") (pintype "passive"))
    )
    (net (code "149") (name "unconnected-(J10-Pad13)") (class "Default")
      (node (ref "J10") (pin "13") (pinfunction "13_13") (pintype "passive"))
    )
    (net (code "150") (name "unconnected-(J10-Pad14)") (class "Default")
      (node (ref "J10") (pin "14") (pinfunction "14_14") (pintype "passive"))
    )
    (net (code "151") (name "unconnected-(J10-Pad15)") (class "Default")
      (node (ref "J10") (pin "15") (pinfunction "15_15") (pintype "passive"))
    )
    (net (code "152") (name "unconnected-(J10-Pad16)") (class "Default")
      (node (ref "J10") (pin "16") (pinfunction "16_16") (pintype "passive"))
    )
    (net (code "153") (name "unconnected-(U$1-PadNC1)") (class "Default")
      (node (ref "U$1") (pin "NC1") (pinfunction "NC1_NC1") (pintype "bidirectional"))
    )
    (net (code "154") (name "unconnected-(U$1-PadNC2)") (class "Default")
      (node (ref "U$1") (pin "NC2") (pinfunction "NC2_NC2") (pintype "bidirectional"))
    )
    (net (code "155") (name "unconnected-(UC2-PB0(ICP)-Pad12)") (class "Default")
      (node (ref "UC2") (pin "12") (pinfunction "PB0(ICP)_12") (pintype "bidirectional"))
    )
    (net (code "156") (name "unconnected-(UC2-PB1(OC1A)-Pad13)") (class "Default")
      (node (ref "UC2") (pin "13") (pinfunction "PB1(OC1A)_13") (pintype "bidirectional"))
    )
    (net (code "157") (name "unconnected-(UC2-PB2(SS{slash}OC1B)-Pad14)") (class "Default")
      (node (ref "UC2") (pin "14") (pinfunction "PB2(SS/OC1B)_14") (pintype "bidirectional"))
    )
    (net (code "158") (name "unconnected-(UC328DIP-PB0(ICP)-Pad14)") (class "Default")
      (node (ref "UC328DIP") (pin "14") (pinfunction "PB0(ICP)_14") (pintype "bidirectional"))
    )
    (net (code "159") (name "unconnected-(UC328DIP-PB1(OC1A)-Pad15)") (class "Default")
      (node (ref "UC328DIP") (pin "15") (pinfunction "PB1(OC1A)_15") (pintype "bidirectional"))
    )
    (net (code "160") (name "unconnected-(UC328DIP-PB2(SS{slash}OC1B)-Pad16)") (class "Default")
      (node (ref "UC328DIP") (pin "16") (pinfunction "PB2(SS/OC1B)_16") (pintype "bidirectional"))
    )
    (net (code "161") (name "unconnected-(UC328DIP-PC2(ADC2)-Pad25)") (class "Default")
      (node (ref "UC328DIP") (pin "25") (pinfunction "PC2(ADC2)_25") (pintype "bidirectional"))
    )
  )
)
